# theremin_go_2024.net
KiCad netlist of a schematic drawn in EAGLE
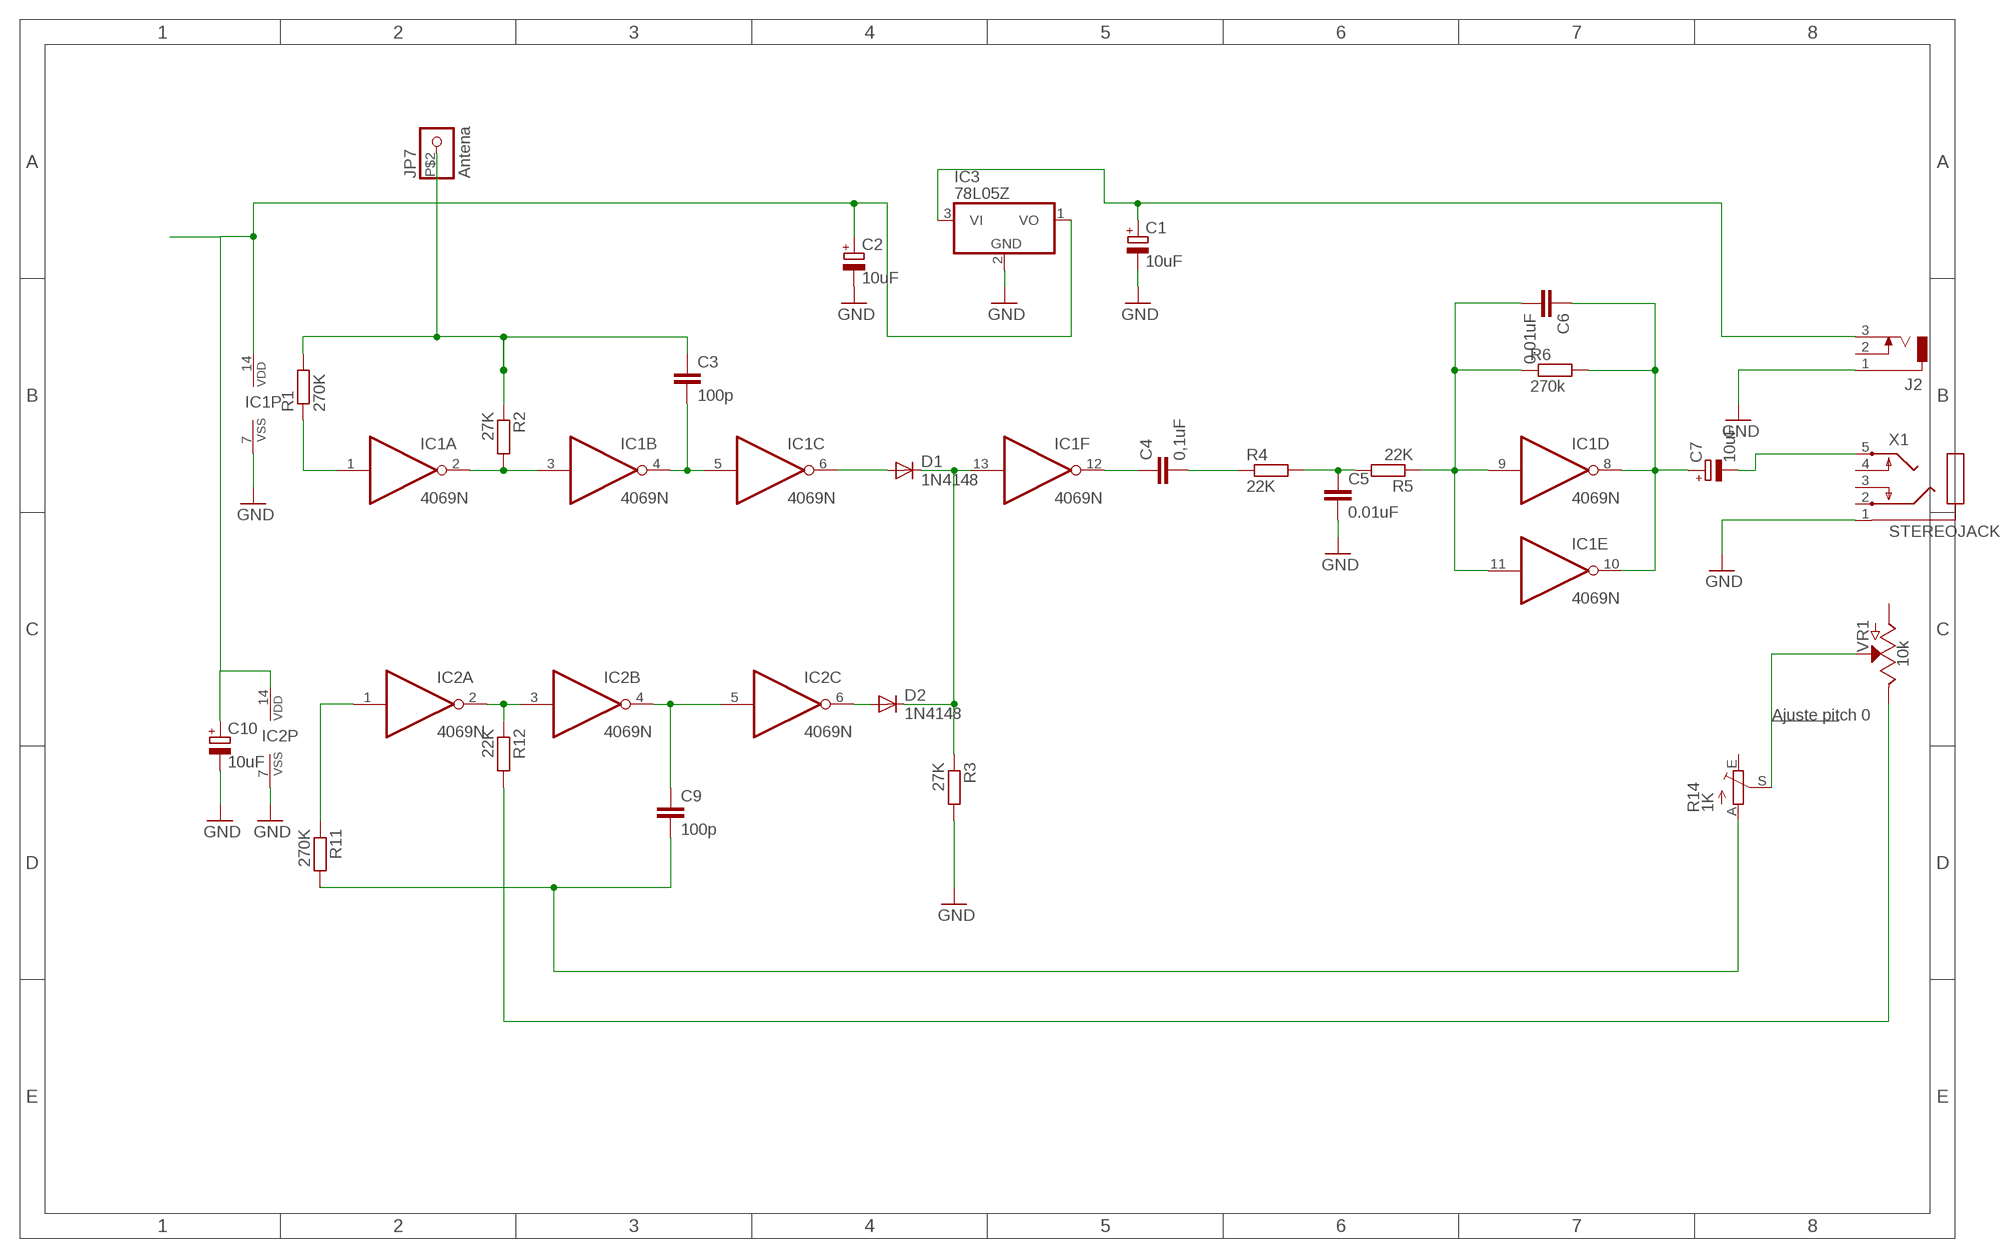
[diagram p0: schematic, sheet 1]

(export (version "E")
  (design (tool "Eeschema 10.0.6"))
  (components
    (comp (ref "C1")
      (value "10uF")
      (footprint "eagle-import:E2,5-6E")
      (libsource (lib "eagle-import") (part "CPOL-EUE2,5-6E"))
    )
    (comp (ref "C2")
      (value "10uF")
      (footprint "eagle-import:E2,5-6E")
      (libsource (lib "eagle-import") (part "CPOL-EUE2,5-6E"))
    )
    (comp (ref "C3")
      (value "100p")
      (footprint "eagle-import:C050-030X075")
      (libsource (lib "eagle-import") (part "C-EU050-030X075"))
    )
    (comp (ref "C4")
      (value "0,1uF")
      (footprint "eagle-import:C050-030X075")
      (libsource (lib "eagle-import") (part "C-EU050-030X075"))
    )
    (comp (ref "C5")
      (value "0.01uF")
      (footprint "eagle-import:C050-030X075")
      (libsource (lib "eagle-import") (part "C-EU050-030X075"))
    )
    (comp (ref "C6")
      (value "0.01uF")
      (footprint "eagle-import:C050-030X075")
      (libsource (lib "eagle-import") (part "C-EU050-030X075"))
    )
    (comp (ref "C7")
      (value "10uF")
      (footprint "eagle-import:E2,5-6E")
      (libsource (lib "eagle-import") (part "CPOL-EUE2,5-6E"))
    )
    (comp (ref "C9")
      (value "100p")
      (footprint "eagle-import:C050-030X075")
      (libsource (lib "eagle-import") (part "C-EU050-030X075"))
    )
    (comp (ref "C10")
      (value "10uF")
      (footprint "eagle-import:E2,5-6E")
      (libsource (lib "eagle-import") (part "CPOL-EUE2,5-6E"))
    )
    (comp (ref "D1")
      (value "1N4148")
      (footprint "eagle-import:DO35-7")
      (libsource (lib "eagle-import") (part "1N4148DO35-7"))
    )
    (comp (ref "D2")
      (value "1N4148")
      (footprint "eagle-import:DO35-7")
      (libsource (lib "eagle-import") (part "1N4148DO35-7"))
    )
    (comp (ref "IC1")
      (value "4069N")
      (footprint "eagle-import:DIL14")
      (libsource (lib "eagle-import") (part "4069N"))
    )
    (comp (ref "IC2")
      (value "4069N")
      (footprint "eagle-import:DIL14")
      (libsource (lib "eagle-import") (part "4069N"))
    )
    (comp (ref "IC3")
      (value "78L05Z")
      (footprint "eagle-import:TO92")
      (libsource (lib "eagle-import") (part "78ZL05"))
    )
    (comp (ref "J2")
      (value "DCJ0303")
      (footprint "eagle-import:DCJ0303")
      (libsource (lib "eagle-import") (part "DCJ0303"))
    )
    (comp (ref "JP7")
      (value "Antena")
      (footprint "eagle-import:1X01")
      (libsource (lib "eagle-import") (part "PINHD-1X1"))
    )
    (comp (ref "R1")
      (value "270K")
      (footprint "eagle-import:0309_10")
      (libsource (lib "eagle-import") (part "R-EU_0309/10"))
    )
    (comp (ref "R2")
      (value "27K")
      (footprint "eagle-import:0309_10")
      (libsource (lib "eagle-import") (part "R-EU_0309/10"))
    )
    (comp (ref "R3")
      (value "27K")
      (footprint "eagle-import:0309_10")
      (libsource (lib "eagle-import") (part "R-EU_0309/10"))
    )
    (comp (ref "R4")
      (value "22K")
      (footprint "eagle-import:0309_10")
      (libsource (lib "eagle-import") (part "R-EU_0309/10"))
    )
    (comp (ref "R5")
      (value "22K")
      (footprint "eagle-import:0309_10")
      (libsource (lib "eagle-import") (part "R-EU_0309/10"))
    )
    (comp (ref "R6")
      (value "270k")
      (footprint "eagle-import:0309_10")
      (libsource (lib "eagle-import") (part "R-EU_0309/10"))
    )
    (comp (ref "R11")
      (value "270K")
      (footprint "eagle-import:0309_10")
      (libsource (lib "eagle-import") (part "R-EU_0309/10"))
    )
    (comp (ref "R12")
      (value "22K")
      (footprint "eagle-import:0309_10")
      (libsource (lib "eagle-import") (part "R-EU_0309/10"))
    )
    (comp (ref "R14")
      (value "1K")
      (footprint "eagle-import:S64W")
      (libsource (lib "eagle-import") (part "TRIM_EU-S64W"))
    )
    (comp (ref "VR1")
      (value "10k")
      (footprint "eagle-import:POT-PTH-ALPS")
      (libsource (lib "eagle-import") (part "POTENTIOMETER-PTH-9MM-1/20W-20%"))
    )
    (comp (ref "X1")
      (value "STEREOJACK")
      (footprint "eagle-import:STX3100")
      (libsource (lib "eagle-import") (part "STEREOJACK"))
    )
  )
  (nets
    (net (code "1") (name "GND") (class "Default")
      (node (ref "C1") (pin "-") (pinfunction "-_-") (pintype "passive"))
      (node (ref "C10") (pin "-") (pinfunction "-_-") (pintype "passive"))
      (node (ref "C2") (pin "-") (pinfunction "-_-") (pintype "passive"))
      (node (ref "C5") (pin "2") (pinfunction "2_2") (pintype "passive"))
      (node (ref "IC1") (pin "7") (pinfunction "VSS_7") (pintype "power_in"))
      (node (ref "IC2") (pin "7") (pinfunction "VSS_7") (pintype "power_in"))
      (node (ref "IC3") (pin "2") (pinfunction "GND_2") (pintype "passive"))
      (node (ref "J2") (pin "1") (pinfunction "1_1") (pintype "passive"))
      (node (ref "R3") (pin "2") (pinfunction "2_2") (pintype "passive"))
      (node (ref "X1") (pin "1") (pinfunction "1_1") (pintype "passive"))
    )
    (net (code "2") (name "Net-(C4-Pad2)") (class "Default")
      (node (ref "C4") (pin "2") (pinfunction "2_2") (pintype "passive"))
      (node (ref "R4") (pin "1") (pinfunction "1_1") (pintype "passive"))
    )
    (net (code "3") (name "Net-(C5-Pad1)") (class "Default")
      (node (ref "C5") (pin "1") (pinfunction "1_1") (pintype "passive"))
      (node (ref "R4") (pin "2") (pinfunction "2_2") (pintype "passive"))
      (node (ref "R5") (pin "2") (pinfunction "2_2") (pintype "passive"))
    )
    (net (code "4") (name "Net-(C7-Pad-)") (class "Default")
      (node (ref "C7") (pin "-") (pinfunction "-_-") (pintype "passive"))
      (node (ref "X1") (pin "5") (pinfunction "5_5") (pintype "passive"))
    )
    (net (code "5") (name "Net-(C9-Pad2)") (class "Default")
      (node (ref "C9") (pin "2") (pinfunction "2_2") (pintype "passive"))
      (node (ref "R11") (pin "2") (pinfunction "2_2") (pintype "passive"))
      (node (ref "R14") (pin "A") (pinfunction "A_A") (pintype "passive"))
    )
    (net (code "6") (name "Net-(IC1A-I)") (class "Default")
      (node (ref "IC1") (pin "1") (pinfunction "I_1") (pintype "input"))
      (node (ref "R1") (pin "1") (pinfunction "1_1") (pintype "passive"))
    )
    (net (code "7") (name "Net-(IC1A-O)") (class "Default")
      (node (ref "IC1") (pin "2") (pinfunction "O_2") (pintype "output"))
      (node (ref "IC1") (pin "3") (pinfunction "I_3") (pintype "input"))
      (node (ref "R2") (pin "2") (pinfunction "2_2") (pintype "passive"))
    )
    (net (code "8") (name "Net-(IC1B-O)") (class "Default")
      (node (ref "C3") (pin "2") (pinfunction "2_2") (pintype "passive"))
      (node (ref "IC1") (pin "4") (pinfunction "O_4") (pintype "output"))
      (node (ref "IC1") (pin "5") (pinfunction "I_5") (pintype "input"))
    )
    (net (code "9") (name "Net-(IC1C-O)") (class "Default")
      (node (ref "D1") (pin "A") (pinfunction "A_A") (pintype "passive"))
      (node (ref "IC1") (pin "6") (pinfunction "O_6") (pintype "output"))
    )
    (net (code "10") (name "Net-(IC1D-I)") (class "Default")
      (node (ref "C6") (pin "2") (pinfunction "2_2") (pintype "passive"))
      (node (ref "IC1") (pin "11") (pinfunction "I_11") (pintype "input"))
      (node (ref "IC1") (pin "9") (pinfunction "I_9") (pintype "input"))
      (node (ref "R5") (pin "1") (pinfunction "1_1") (pintype "passive"))
      (node (ref "R6") (pin "1") (pinfunction "1_1") (pintype "passive"))
    )
    (net (code "11") (name "Net-(IC1D-O)") (class "Default")
      (node (ref "C6") (pin "1") (pinfunction "1_1") (pintype "passive"))
      (node (ref "C7") (pin "+") (pinfunction "+_+") (pintype "passive"))
      (node (ref "IC1") (pin "10") (pinfunction "O_10") (pintype "output"))
      (node (ref "IC1") (pin "8") (pinfunction "O_8") (pintype "output"))
      (node (ref "R6") (pin "2") (pinfunction "2_2") (pintype "passive"))
    )
    (net (code "12") (name "Net-(IC1F-I)") (class "Default")
      (node (ref "D1") (pin "C") (pinfunction "C_C") (pintype "passive"))
      (node (ref "D2") (pin "C") (pinfunction "C_C") (pintype "passive"))
      (node (ref "IC1") (pin "13") (pinfunction "I_13") (pintype "input"))
      (node (ref "R3") (pin "1") (pinfunction "1_1") (pintype "passive"))
    )
    (net (code "13") (name "Net-(IC1F-O)") (class "Default")
      (node (ref "C4") (pin "1") (pinfunction "1_1") (pintype "passive"))
      (node (ref "IC1") (pin "12") (pinfunction "O_12") (pintype "output"))
    )
    (net (code "14") (name "Net-(IC1G-VDD)") (class "Default")
      (node (ref "C10") (pin "+") (pinfunction "+_+") (pintype "passive"))
      (node (ref "C2") (pin "+") (pinfunction "+_+") (pintype "passive"))
      (node (ref "IC1") (pin "14") (pinfunction "VDD_14") (pintype "power_in"))
      (node (ref "IC2") (pin "14") (pinfunction "VDD_14") (pintype "power_in"))
      (node (ref "IC3") (pin "1") (pinfunction "VO_1") (pintype "passive"))
    )
    (net (code "15") (name "Net-(IC2A-I)") (class "Default")
      (node (ref "IC2") (pin "1") (pinfunction "I_1") (pintype "input"))
      (node (ref "R11") (pin "1") (pinfunction "1_1") (pintype "passive"))
    )
    (net (code "16") (name "Net-(IC2A-O)") (class "Default")
      (node (ref "IC2") (pin "2") (pinfunction "O_2") (pintype "output"))
      (node (ref "IC2") (pin "3") (pinfunction "I_3") (pintype "input"))
      (node (ref "R12") (pin "1") (pinfunction "1_1") (pintype "passive"))
    )
    (net (code "17") (name "Net-(IC2B-O)") (class "Default")
      (node (ref "C9") (pin "1") (pinfunction "1_1") (pintype "passive"))
      (node (ref "IC2") (pin "4") (pinfunction "O_4") (pintype "output"))
      (node (ref "IC2") (pin "5") (pinfunction "I_5") (pintype "input"))
    )
    (net (code "18") (name "Net-(IC2C-O)") (class "Default")
      (node (ref "D2") (pin "A") (pinfunction "A_A") (pintype "passive"))
      (node (ref "IC2") (pin "6") (pinfunction "O_6") (pintype "output"))
    )
    (net (code "19") (name "Net-(IC3-VI)") (class "Default")
      (node (ref "C1") (pin "+") (pinfunction "+_+") (pintype "passive"))
      (node (ref "IC3") (pin "3") (pinfunction "VI_3") (pintype "input"))
      (node (ref "J2") (pin "3") (pinfunction "3_3") (pintype "passive"))
    )
    (net (code "20") (name "Net-(JP7-1)") (class "Default")
      (node (ref "C3") (pin "1") (pinfunction "1_1") (pintype "passive"))
      (node (ref "JP7") (pin "P$2") (pinfunction "1_P$2") (pintype "passive"))
      (node (ref "R1") (pin "2") (pinfunction "2_2") (pintype "passive"))
      (node (ref "R2") (pin "1") (pinfunction "1_1") (pintype "passive"))
    )
    (net (code "21") (name "Net-(VR1-E)") (class "Default")
      (node (ref "R12") (pin "2") (pinfunction "2_2") (pintype "passive"))
      (node (ref "VR1") (pin "P$1") (pinfunction "E_P$1") (pintype "passive"))
    )
    (net (code "22") (name "Net-(VR1-S)") (class "Default")
      (node (ref "R14") (pin "S") (pinfunction "S_S") (pintype "passive"))
      (node (ref "VR1") (pin "P$2") (pinfunction "S_P$2") (pintype "passive"))
    )
    (net (code "23") (name "unconnected-(J2-Pad2)") (class "Default")
      (node (ref "J2") (pin "2") (pinfunction "2_2") (pintype "passive"))
    )
    (net (code "24") (name "unconnected-(R14-PadE)") (class "Default")
      (node (ref "R14") (pin "E") (pinfunction "E_E") (pintype "passive"))
    )
    (net (code "25") (name "unconnected-(VR1-A-PadP$3)") (class "Default")
      (node (ref "VR1") (pin "P$3") (pinfunction "A_P$3") (pintype "passive"))
    )
    (net (code "26") (name "unconnected-(X1-Pad2)") (class "Default")
      (node (ref "X1") (pin "2") (pinfunction "2_2") (pintype "passive"))
    )
    (net (code "27") (name "unconnected-(X1-Pad3)") (class "Default")
      (node (ref "X1") (pin "3") (pinfunction "3_3") (pintype "passive"))
    )
    (net (code "28") (name "unconnected-(X1-Pad4)") (class "Default")
      (node (ref "X1") (pin "4") (pinfunction "4_4") (pintype "passive"))
    )
  )
)
